# 7_09_6.net
KiCad netlist of a schematic drawn in Altium Designer
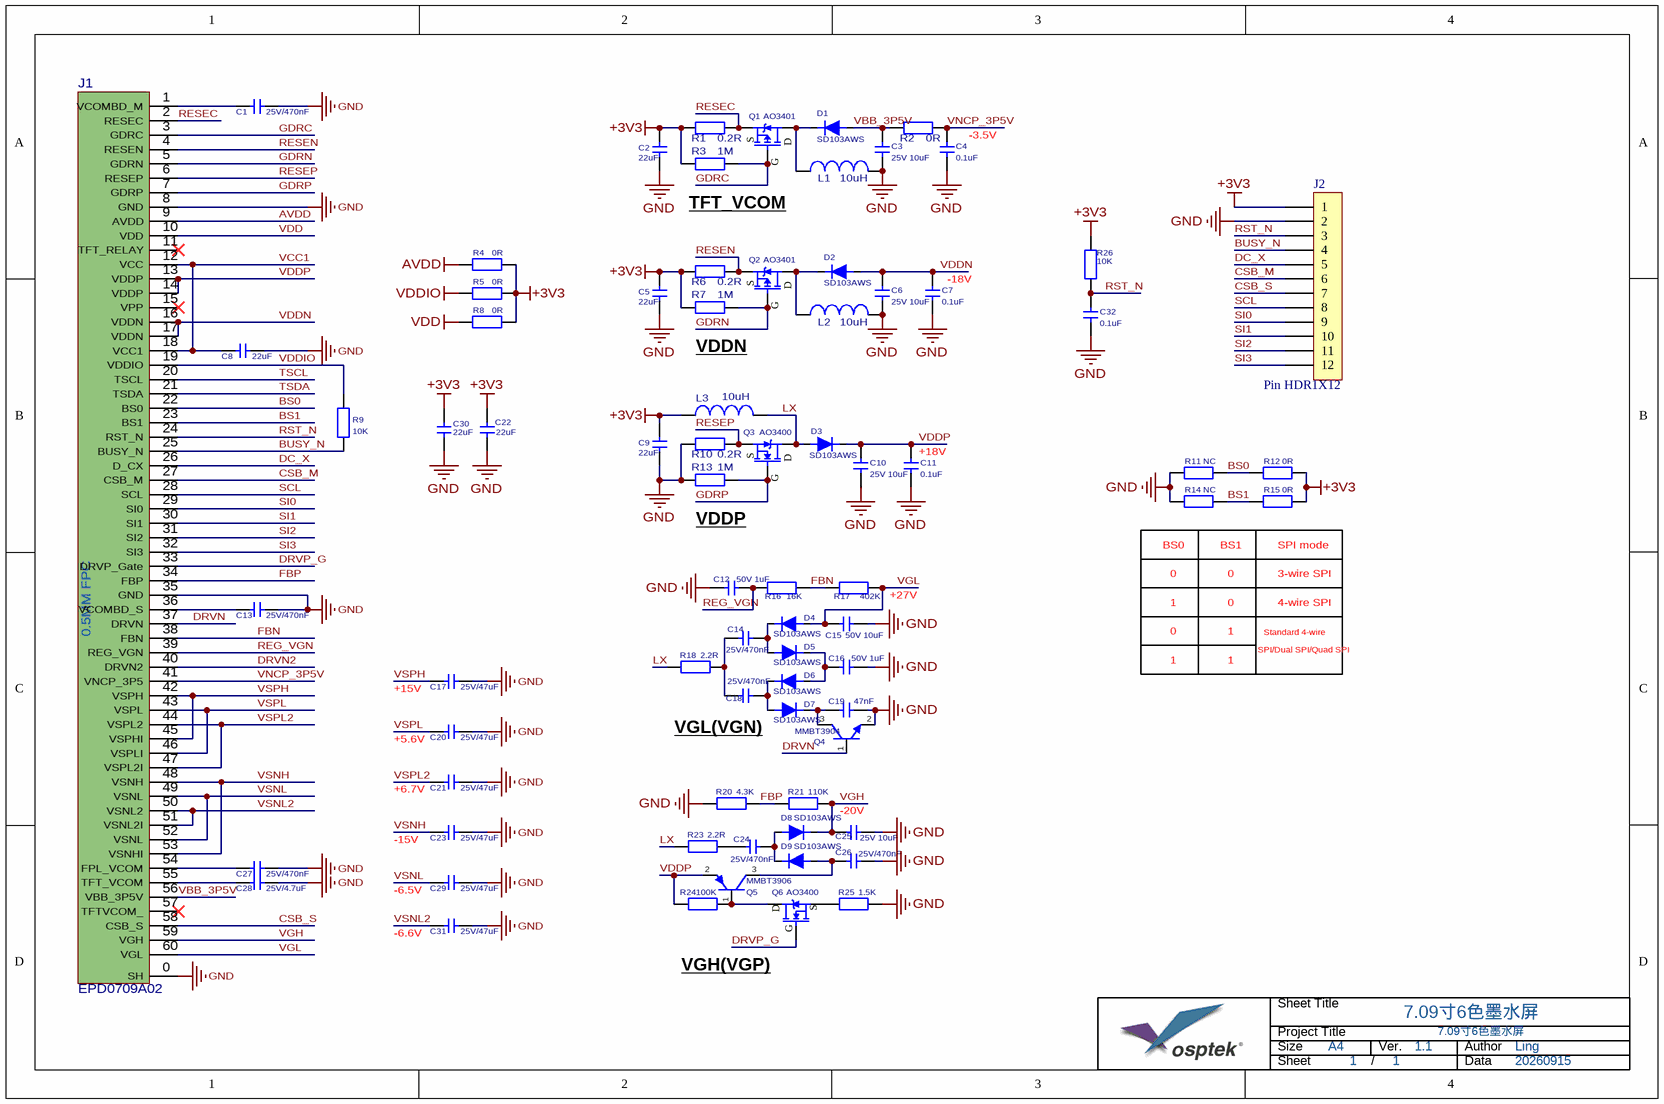
[diagram p0: 7.09寸6色墨水屏.SchDoc]

(export (version "E")
  (design (tool "Eeschema 10.0.6"))
  (components
    (comp (ref "C1")
      (value "25V/470nF")
      (footprint "0603-C")
      (description "Capacitor")
      (libsource (lib "ODG_AD_Lib") (part "CAP"))
    )
    (comp (ref "C2")
      (value "22uF")
      (footprint "0603-C")
      (description "Capacitor")
      (libsource (lib "ODG_AD_Lib") (part "CAP"))
    )
    (comp (ref "C3")
      (value "25V 10uF")
      (footprint "0805-C")
      (description "Capacitor")
      (libsource (lib "ODG_AD_Lib") (part "CAP"))
    )
    (comp (ref "C4")
      (value "0.1uF")
      (footprint "0603-C")
      (description "Capacitor")
      (libsource (lib "ODG_AD_Lib") (part "CAP"))
    )
    (comp (ref "C5")
      (value "22uF")
      (footprint "0603-C")
      (description "Capacitor")
      (libsource (lib "ODG_AD_Lib") (part "CAP"))
    )
    (comp (ref "C6")
      (value "25V 10uF")
      (footprint "0805-C")
      (description "Capacitor")
      (libsource (lib "ODG_AD_Lib") (part "CAP"))
    )
    (comp (ref "C7")
      (value "0.1uF")
      (footprint "0603-C")
      (description "Capacitor")
      (libsource (lib "ODG_AD_Lib") (part "CAP"))
    )
    (comp (ref "C8")
      (value "22uF")
      (footprint "0603-C")
      (description "Capacitor")
      (libsource (lib "ODG_AD_Lib") (part "CAP"))
    )
    (comp (ref "C9")
      (value "22uF")
      (footprint "0603-C")
      (description "Capacitor")
      (libsource (lib "ODG_AD_Lib") (part "CAP"))
    )
    (comp (ref "C10")
      (value "25V 10uF")
      (footprint "0805-C")
      (description "Capacitor")
      (libsource (lib "ODG_AD_Lib") (part "CAP"))
    )
    (comp (ref "C11")
      (value "0.1uF")
      (footprint "0603-C")
      (description "Capacitor")
      (libsource (lib "ODG_AD_Lib") (part "CAP"))
    )
    (comp (ref "C12")
      (value "50V 1uF")
      (footprint "0603-C")
      (description "Capacitor")
      (libsource (lib "ODG_AD_Lib") (part "CAP"))
    )
    (comp (ref "C13")
      (value "25V/470nF")
      (footprint "0603-C")
      (description "Capacitor")
      (libsource (lib "ODG_AD_Lib") (part "CAP"))
    )
    (comp (ref "C14")
      (value "25V/470nF")
      (footprint "0603-C")
      (description "Capacitor")
      (libsource (lib "ODG_AD_Lib") (part "CAP"))
    )
    (comp (ref "C15")
      (value "50V 10uF")
      (footprint "0805-C")
      (description "Capacitor")
      (libsource (lib "ODG_AD_Lib") (part "CAP"))
    )
    (comp (ref "C16")
      (value "50V 1uF")
      (footprint "0603-C")
      (description "Capacitor")
      (libsource (lib "ODG_AD_Lib") (part "CAP"))
    )
    (comp (ref "C17")
      (value "25V/47uF")
      (footprint "1206/3216 C3")
      (description "Capacitor")
      (libsource (lib "ODG_AD_Lib") (part "CAP"))
    )
    (comp (ref "C18")
      (value "25V/470nF")
      (footprint "0603-C")
      (description "Capacitor")
      (libsource (lib "ODG_AD_Lib") (part "CAP"))
    )
    (comp (ref "C19")
      (value "47nF")
      (footprint "0603-C")
      (description "Capacitor")
      (libsource (lib "ODG_AD_Lib") (part "CAP"))
    )
    (comp (ref "C20")
      (value "25V/47uF")
      (footprint "1206/3216 C3")
      (description "Capacitor")
      (libsource (lib "ODG_AD_Lib") (part "CAP"))
    )
    (comp (ref "C21")
      (value "25V/47uF")
      (footprint "1206/3216 C3")
      (description "Capacitor")
      (libsource (lib "ODG_AD_Lib") (part "CAP"))
    )
    (comp (ref "C22")
      (value "22uF")
      (footprint "0603-C")
      (description "Capacitor")
      (libsource (lib "ODG_AD_Lib") (part "CAP"))
    )
    (comp (ref "C23")
      (value "25V/47uF")
      (footprint "1206/3216 C3")
      (description "Capacitor")
      (libsource (lib "ODG_AD_Lib") (part "CAP"))
    )
    (comp (ref "C24")
      (value "25V/470nF")
      (footprint "0603-C")
      (description "Capacitor")
      (libsource (lib "ODG_AD_Lib") (part "CAP"))
    )
    (comp (ref "C25")
      (value "25V 10uF")
      (footprint "0805-C")
      (description "Capacitor")
      (libsource (lib "ODG_AD_Lib") (part "CAP"))
    )
    (comp (ref "C26")
      (value "25V/470nF")
      (footprint "0603-C")
      (description "Capacitor")
      (libsource (lib "ODG_AD_Lib") (part "CAP"))
    )
    (comp (ref "C27")
      (value "25V/470nF")
      (footprint "0603-C")
      (description "Capacitor")
      (libsource (lib "ODG_AD_Lib") (part "CAP"))
    )
    (comp (ref "C28")
      (value "25V/4.7uF")
      (footprint "0603-C")
      (description "Capacitor")
      (libsource (lib "ODG_AD_Lib") (part "CAP"))
    )
    (comp (ref "C29")
      (value "25V/47uF")
      (footprint "1206/3216 C3")
      (description "Capacitor")
      (libsource (lib "ODG_AD_Lib") (part "CAP"))
    )
    (comp (ref "C30")
      (value "22uF")
      (footprint "0603-C")
      (description "Capacitor")
      (libsource (lib "ODG_AD_Lib") (part "CAP"))
    )
    (comp (ref "C31")
      (value "25V/47uF")
      (footprint "1206/3216 C3")
      (description "Capacitor")
      (libsource (lib "ODG_AD_Lib") (part "CAP"))
    )
    (comp (ref "C32")
      (value "0.1uF")
      (footprint "0603-C")
      (description "Capacitor")
      (libsource (lib "ODG_AD_Lib") (part "CAP"))
    )
    (comp (ref "D1") (value "SD103AWS") (footprint "SOD-323") (libsource (lib "CZ-NB部分") (part "DSK110")))
    (comp (ref "D2") (value "SD103AWS") (footprint "SOD-323") (libsource (lib "CZ-NB部分") (part "DSK110")))
    (comp (ref "D3") (value "SD103AWS") (footprint "SOD-323") (libsource (lib "CZ-NB部分") (part "DSK110")))
    (comp (ref "D4") (value "SD103AWS") (footprint "SOD-323") (libsource (lib "CZ-NB部分") (part "DSK110")))
    (comp (ref "D5") (value "SD103AWS") (footprint "SOD-323") (libsource (lib "CZ-NB部分") (part "DSK110")))
    (comp (ref "D6") (value "SD103AWS") (footprint "SOD-323") (libsource (lib "CZ-NB部分") (part "DSK110")))
    (comp (ref "D7") (value "SD103AWS") (footprint "SOD-323") (libsource (lib "CZ-NB部分") (part "DSK110")))
    (comp (ref "D8") (value "SD103AWS") (footprint "SOD-323") (libsource (lib "CZ-NB部分") (part "DSK110")))
    (comp (ref "D9") (value "SD103AWS") (footprint "SOD-323") (libsource (lib "CZ-NB部分") (part "DSK110")))
    (comp (ref "J1")
      (value "EPD0709A02")
      (footprint "FPC0.5-60P")
      (libsource (lib "ESP32P4C5模组") (part "EPD0709A02"))
    )
    (comp (ref "J2")
      (value "Pin HDR1X12")
      (footprint "Pin HDR1X12/2.54mm-S")
      (libsource (lib "排针") (part "Pin HDR1X12"))
    )
    (comp (ref "L1")
      (value "10uH")
      (footprint "IND_CB2518_MM")
      (description "INDUCTOR")
      (libsource (lib "电感") (part "INDUCTOR"))
    )
    (comp (ref "L2")
      (value "10uH")
      (footprint "IND_CB2518_MM")
      (description "INDUCTOR")
      (libsource (lib "电感") (part "INDUCTOR"))
    )
    (comp (ref "L3")
      (value "10uH")
      (footprint "IND_CB2518_MM")
      (description "INDUCTOR")
      (libsource (lib "电感") (part "INDUCTOR"))
    )
    (comp (ref "Q1")
      (value "AO3401")
      (footprint "SOT-23-3")
      (description "P沟道 30V/4.2A")
      (libsource (lib "6.1   - 场效应管-可控硅") (part "AO3401"))
    )
    (comp (ref "Q2")
      (value "AO3401")
      (footprint "SOT-23-3")
      (description "P沟道 30V/4.2A")
      (libsource (lib "6.1   - 场效应管-可控硅") (part "AO3401"))
    )
    (comp (ref "Q3")
      (value "AO3400")
      (footprint "SOT-23-3")
      (description "N沟道 30V/4.2A")
      (libsource (lib "6.1   - 场效应管-可控硅") (part "AO3400"))
    )
    (comp (ref "Q4")
      (value "MMBT3904")
      (footprint "SOT-23-3")
      (description "NPN Bipolar Transistor")
      (fields (field (name "PUBLISHER") "Altium Limited"))
      (libsource (lib "Miscellaneous Devices") (part "NPN"))
    )
    (comp (ref "Q5")
      (value "MMBT3906")
      (footprint "SOT-23-3")
      (description "NPN Bipolar Transistor")
      (fields (field (name "PUBLISHER") "Altium Limited"))
      (libsource (lib "ESP32P4C5模组") (part "PNP"))
    )
    (comp (ref "Q6")
      (value "AO3400")
      (footprint "SOT-23-3")
      (description "N沟道 30V/4.2A")
      (libsource (lib "6.1   - 场效应管-可控硅") (part "AO3400"))
    )
    (comp (ref "R1")
      (value "0.2R")
      (footprint "0603-R")
      (description "Resistor")
      (fields (field (name "PUBLISHER") "*"))
      (libsource (lib "*") (part "Res2"))
    )
    (comp (ref "R2")
      (value "0R")
      (footprint "0603-R")
      (description "Resistor")
      (fields (field (name "PUBLISHER") "*"))
      (libsource (lib "*") (part "Res2"))
    )
    (comp (ref "R3")
      (value "1M")
      (footprint "0603-R")
      (description "Resistor")
      (fields (field (name "PUBLISHER") "*"))
      (libsource (lib "*") (part "Res2"))
    )
    (comp (ref "R4")
      (value "0R")
      (footprint "0603-R")
      (description "Resistor")
      (fields (field (name "PUBLISHER") "*"))
      (libsource (lib "") (part "Res2_1"))
    )
    (comp (ref "R5")
      (value "0R")
      (footprint "0603-R")
      (description "Resistor")
      (fields (field (name "PUBLISHER") "*"))
      (libsource (lib "") (part "Res2_1"))
    )
    (comp (ref "R6")
      (value "0.2R")
      (footprint "0603-R")
      (description "Resistor")
      (fields (field (name "PUBLISHER") "*"))
      (libsource (lib "*") (part "Res2"))
    )
    (comp (ref "R7")
      (value "1M")
      (footprint "0603-R")
      (description "Resistor")
      (fields (field (name "PUBLISHER") "*"))
      (libsource (lib "*") (part "Res2"))
    )
    (comp (ref "R8")
      (value "0R")
      (footprint "0603-R")
      (description "Resistor")
      (fields (field (name "PUBLISHER") "*"))
      (libsource (lib "") (part "Res2_1"))
    )
    (comp (ref "R9")
      (value "10K")
      (footprint "0603-R")
      (description "Resistor")
      (fields (field (name "PUBLISHER") "*"))
      (libsource (lib "") (part "Res2_2"))
    )
    (comp (ref "R10")
      (value "0.2R")
      (footprint "0603-R")
      (description "Resistor")
      (fields (field (name "PUBLISHER") "*"))
      (libsource (lib "*") (part "Res2"))
    )
    (comp (ref "R11")
      (value "NC")
      (footprint "0603-R")
      (description "Resistor")
      (fields (field (name "PUBLISHER") "*"))
      (libsource (lib "") (part "Res2_1"))
    )
    (comp (ref "R12")
      (value "0R")
      (footprint "0603-R")
      (description "Resistor")
      (fields (field (name "PUBLISHER") "*"))
      (libsource (lib "") (part "Res2_1"))
    )
    (comp (ref "R13")
      (value "1M")
      (footprint "0603-R")
      (description "Resistor")
      (fields (field (name "PUBLISHER") "*"))
      (libsource (lib "*") (part "Res2"))
    )
    (comp (ref "R14")
      (value "NC")
      (footprint "0603-R")
      (description "Resistor")
      (fields (field (name "PUBLISHER") "*"))
      (libsource (lib "") (part "Res2_1"))
    )
    (comp (ref "R15")
      (value "0R")
      (footprint "0603-R")
      (description "Resistor")
      (fields (field (name "PUBLISHER") "*"))
      (libsource (lib "") (part "Res2_1"))
    )
    (comp (ref "R16")
      (value "16K")
      (footprint "0603-R")
      (description "Resistor")
      (fields (field (name "PUBLISHER") "*"))
      (libsource (lib "*") (part "Res2"))
    )
    (comp (ref "R17")
      (value "402K")
      (footprint "0603-R")
      (description "Resistor")
      (fields (field (name "PUBLISHER") "*"))
      (libsource (lib "*") (part "Res2"))
    )
    (comp (ref "R18")
      (value "2.2R")
      (footprint "0603-R")
      (description "Resistor")
      (fields (field (name "PUBLISHER") "*"))
      (libsource (lib "*") (part "Res2"))
    )
    (comp (ref "R20")
      (value "4.3K")
      (footprint "0603-R")
      (description "Resistor")
      (fields (field (name "PUBLISHER") "*"))
      (libsource (lib "*") (part "Res2"))
    )
    (comp (ref "R21")
      (value "110K")
      (footprint "0603-R")
      (description "Resistor")
      (fields (field (name "PUBLISHER") "*"))
      (libsource (lib "*") (part "Res2"))
    )
    (comp (ref "R23")
      (value "2.2R")
      (footprint "0603-R")
      (description "Resistor")
      (fields (field (name "PUBLISHER") "*"))
      (libsource (lib "*") (part "Res2"))
    )
    (comp (ref "R24")
      (value "100K")
      (footprint "0603-R")
      (description "Resistor")
      (fields (field (name "PUBLISHER") "*"))
      (libsource (lib "*") (part "Res2"))
    )
    (comp (ref "R25")
      (value "1.5K")
      (footprint "0603-R")
      (description "Resistor")
      (fields (field (name "PUBLISHER") "*"))
      (libsource (lib "*") (part "Res2"))
    )
    (comp (ref "R26")
      (value "10K")
      (footprint "0603-R")
      (description "Resistor")
      (fields (field (name "PUBLISHER") "*"))
      (libsource (lib "") (part "Res2_3"))
    )
  )
  (nets
    (net (code "1") (name "+3V3") (class "Default")
      (node (ref "C2") (pin "2") (pinfunction "2_2") (pintype "passive"))
      (node (ref "C22") (pin "2") (pinfunction "2_2") (pintype "passive"))
      (node (ref "C30") (pin "1") (pinfunction "1_1") (pintype "passive"))
      (node (ref "C5") (pin "2") (pinfunction "2_2") (pintype "passive"))
      (node (ref "C9") (pin "2") (pinfunction "2_2") (pintype "passive"))
      (node (ref "J2") (pin "1") (pinfunction "1_1") (pintype "passive"))
      (node (ref "L3") (pin "2") (pinfunction "2_2") (pintype "passive"))
      (node (ref "R1") (pin "2") (pinfunction "2_2") (pintype "passive"))
      (node (ref "R12") (pin "2") (pinfunction "2_2") (pintype "passive"))
      (node (ref "R15") (pin "2") (pinfunction "2_2") (pintype "passive"))
      (node (ref "R26") (pin "2") (pinfunction "2_2") (pintype "passive"))
      (node (ref "R3") (pin "2") (pinfunction "2_2") (pintype "passive"))
      (node (ref "R4") (pin "2") (pinfunction "2_2") (pintype "passive"))
      (node (ref "R5") (pin "2") (pinfunction "2_2") (pintype "passive"))
      (node (ref "R6") (pin "2") (pinfunction "2_2") (pintype "passive"))
      (node (ref "R7") (pin "2") (pinfunction "2_2") (pintype "passive"))
      (node (ref "R8") (pin "2") (pinfunction "2_2") (pintype "passive"))
    )
    (net (code "2") (name "/BS0") (class "Default")
      (node (ref "J1") (pin "22") (pinfunction "BS0_22") (pintype "passive"))
      (node (ref "R11") (pin "2") (pinfunction "2_2") (pintype "passive"))
      (node (ref "R12") (pin "1") (pinfunction "1_1") (pintype "passive"))
    )
    (net (code "3") (name "/BS1") (class "Default")
      (node (ref "J1") (pin "23") (pinfunction "BS1_23") (pintype "passive"))
      (node (ref "R14") (pin "2") (pinfunction "2_2") (pintype "passive"))
      (node (ref "R15") (pin "1") (pinfunction "1_1") (pintype "passive"))
    )
    (net (code "4") (name "/BUSY_N") (class "Default")
      (node (ref "J1") (pin "25") (pinfunction "BUSY_N_25") (pintype "passive"))
      (node (ref "J2") (pin "4") (pinfunction "4_4") (pintype "passive"))
      (node (ref "R9") (pin "2") (pinfunction "2_2") (pintype "passive"))
    )
    (net (code "5") (name "/CSB_M") (class "Default")
      (node (ref "J1") (pin "27") (pinfunction "CSB_M_27") (pintype "passive"))
      (node (ref "J2") (pin "6") (pinfunction "6_6") (pintype "passive"))
    )
    (net (code "6") (name "/CSB_S") (class "Default")
      (node (ref "J1") (pin "58") (pinfunction "CSB_S_58") (pintype "passive"))
      (node (ref "J2") (pin "7") (pinfunction "7_7") (pintype "passive"))
    )
    (net (code "7") (name "/DC_X") (class "Default")
      (node (ref "J1") (pin "26") (pinfunction "D_CX_26") (pintype "passive"))
      (node (ref "J2") (pin "5") (pinfunction "5_5") (pintype "passive"))
    )
    (net (code "8") (name "/DRVN") (class "Default")
      (node (ref "J1") (pin "37") (pinfunction "DRVN_37") (pintype "passive"))
      (node (ref "Q4") (pin "1") (pinfunction "B_1") (pintype "passive"))
    )
    (net (code "9") (name "/DRVN2") (class "Default")
      (node (ref "J1") (pin "40") (pinfunction "DRVN2_40") (pintype "passive"))
    )
    (net (code "10") (name "/DRVP_G") (class "Default")
      (node (ref "J1") (pin "33") (pinfunction "DRVP_Gate_33") (pintype "passive"))
      (node (ref "Q6") (pin "1") (pinfunction "G_1") (pintype "passive"))
    )
    (net (code "11") (name "/FBN") (class "Default")
      (node (ref "J1") (pin "38") (pinfunction "FBN_38") (pintype "passive"))
      (node (ref "R16") (pin "1") (pinfunction "1_1") (pintype "passive"))
      (node (ref "R17") (pin "2") (pinfunction "2_2") (pintype "passive"))
    )
    (net (code "12") (name "/FBP") (class "Default")
      (node (ref "J1") (pin "34") (pinfunction "FBP_34") (pintype "passive"))
      (node (ref "R20") (pin "1") (pinfunction "1_1") (pintype "passive"))
      (node (ref "R21") (pin "2") (pinfunction "2_2") (pintype "passive"))
    )
    (net (code "13") (name "/GDRC") (class "Default")
      (node (ref "J1") (pin "3") (pinfunction "GDRC_3") (pintype "passive"))
      (node (ref "Q1") (pin "1") (pinfunction "G_1") (pintype "passive"))
      (node (ref "R3") (pin "1") (pinfunction "1_1") (pintype "passive"))
    )
    (net (code "14") (name "/GDRN") (class "Default")
      (node (ref "J1") (pin "5") (pinfunction "GDRN_5") (pintype "passive"))
      (node (ref "Q2") (pin "1") (pinfunction "G_1") (pintype "passive"))
      (node (ref "R7") (pin "1") (pinfunction "1_1") (pintype "passive"))
    )
    (net (code "15") (name "/GDRP") (class "Default")
      (node (ref "J1") (pin "7") (pinfunction "GDRP_7") (pintype "passive"))
      (node (ref "Q3") (pin "1") (pinfunction "G_1") (pintype "passive"))
      (node (ref "R13") (pin "1") (pinfunction "1_1") (pintype "passive"))
    )
    (net (code "16") (name "/LX") (class "Default")
      (node (ref "D3") (pin "A") (pinfunction "A_A") (pintype "passive"))
      (node (ref "L3") (pin "1") (pinfunction "1_1") (pintype "passive"))
      (node (ref "Q3") (pin "3") (pinfunction "D_3") (pintype "passive"))
      (node (ref "R18") (pin "2") (pinfunction "2_2") (pintype "passive"))
      (node (ref "R23") (pin "2") (pinfunction "2_2") (pintype "passive"))
    )
    (net (code "17") (name "/REG_VGN") (class "Default")
      (node (ref "C12") (pin "1") (pinfunction "1_1") (pintype "passive"))
      (node (ref "J1") (pin "39") (pinfunction "REG_VGN_39") (pintype "passive"))
      (node (ref "R16") (pin "2") (pinfunction "2_2") (pintype "passive"))
    )
    (net (code "18") (name "/RESEC") (class "Default")
      (node (ref "J1") (pin "2") (pinfunction "RESEC_2") (pintype "passive"))
      (node (ref "Q1") (pin "2") (pinfunction "S_2") (pintype "passive"))
      (node (ref "R1") (pin "1") (pinfunction "1_1") (pintype "passive"))
    )
    (net (code "19") (name "/RESEN") (class "Default")
      (node (ref "J1") (pin "4") (pinfunction "RESEN_4") (pintype "passive"))
      (node (ref "Q2") (pin "2") (pinfunction "S_2") (pintype "passive"))
      (node (ref "R6") (pin "1") (pinfunction "1_1") (pintype "passive"))
    )
    (net (code "20") (name "/RESEP") (class "Default")
      (node (ref "J1") (pin "6") (pinfunction "RESEP_6") (pintype "passive"))
      (node (ref "Q3") (pin "2") (pinfunction "S_2") (pintype "passive"))
      (node (ref "R10") (pin "1") (pinfunction "1_1") (pintype "passive"))
    )
    (net (code "21") (name "/RST_N") (class "Default")
      (node (ref "C32") (pin "2") (pinfunction "2_2") (pintype "passive"))
      (node (ref "J1") (pin "24") (pinfunction "RST_N_24") (pintype "passive"))
      (node (ref "J2") (pin "3") (pinfunction "3_3") (pintype "passive"))
      (node (ref "R26") (pin "1") (pinfunction "1_1") (pintype "passive"))
    )
    (net (code "22") (name "/SCL") (class "Default")
      (node (ref "J1") (pin "28") (pinfunction "SCL_28") (pintype "passive"))
      (node (ref "J2") (pin "8") (pinfunction "8_8") (pintype "passive"))
    )
    (net (code "23") (name "/SI0") (class "Default")
      (node (ref "J1") (pin "29") (pinfunction "SI0_29") (pintype "passive"))
      (node (ref "J2") (pin "9") (pinfunction "9_9") (pintype "passive"))
    )
    (net (code "24") (name "/SI1") (class "Default")
      (node (ref "J1") (pin "30") (pinfunction "SI1_30") (pintype "passive"))
      (node (ref "J2") (pin "10") (pinfunction "10_10") (pintype "passive"))
    )
    (net (code "25") (name "/SI2") (class "Default")
      (node (ref "J1") (pin "31") (pinfunction "SI2_31") (pintype "passive"))
      (node (ref "J2") (pin "11") (pinfunction "11_11") (pintype "passive"))
    )
    (net (code "26") (name "/SI3") (class "Default")
      (node (ref "J1") (pin "32") (pinfunction "SI3_32") (pintype "passive"))
      (node (ref "J2") (pin "12") (pinfunction "12_12") (pintype "passive"))
    )
    (net (code "27") (name "/TSCL") (class "Default")
      (node (ref "J1") (pin "20") (pinfunction "TSCL_20") (pintype "passive"))
    )
    (net (code "28") (name "/TSDA") (class "Default")
      (node (ref "J1") (pin "21") (pinfunction "TSDA_21") (pintype "passive"))
    )
    (net (code "29") (name "/VBB_3P5V") (class "Default")
      (node (ref "C3") (pin "2") (pinfunction "2_2") (pintype "passive"))
      (node (ref "D1") (pin "A") (pinfunction "A_A") (pintype "passive"))
      (node (ref "J1") (pin "56") (pinfunction "VBB_3P5V_56") (pintype "passive"))
      (node (ref "R2") (pin "2") (pinfunction "2_2") (pintype "passive"))
    )
    (net (code "30") (name "/VCC1") (class "Default")
      (node (ref "C8") (pin "1") (pinfunction "1_1") (pintype "passive"))
      (node (ref "J1") (pin "12") (pinfunction "VCC_12") (pintype "passive"))
      (node (ref "J1") (pin "18") (pinfunction "VCC1_18") (pintype "passive"))
    )
    (net (code "31") (name "/VDDN") (class "Default")
      (node (ref "C6") (pin "2") (pinfunction "2_2") (pintype "passive"))
      (node (ref "C7") (pin "2") (pinfunction "2_2") (pintype "passive"))
      (node (ref "D2") (pin "A") (pinfunction "A_A") (pintype "passive"))
      (node (ref "J1") (pin "16") (pinfunction "VDDN_16") (pintype "passive"))
      (node (ref "J1") (pin "17") (pinfunction "VDDN_17") (pintype "passive"))
    )
    (net (code "32") (name "/VDDP") (class "Default")
      (node (ref "C10") (pin "2") (pinfunction "2_2") (pintype "passive"))
      (node (ref "C11") (pin "2") (pinfunction "2_2") (pintype "passive"))
      (node (ref "D3") (pin "K") (pinfunction "K_K") (pintype "passive"))
      (node (ref "J1") (pin "13") (pinfunction "VDDP_13") (pintype "passive"))
      (node (ref "J1") (pin "14") (pinfunction "VDDP_14") (pintype "passive"))
      (node (ref "Q5") (pin "2") (pinfunction "E_2") (pintype "passive"))
      (node (ref "R24") (pin "2") (pinfunction "2_2") (pintype "passive"))
    )
    (net (code "33") (name "/VGH") (class "Default")
      (node (ref "C25") (pin "2") (pinfunction "2_2") (pintype "passive"))
      (node (ref "D8") (pin "K") (pinfunction "K_K") (pintype "passive"))
      (node (ref "J1") (pin "59") (pinfunction "VGH_59") (pintype "passive"))
      (node (ref "R21") (pin "1") (pinfunction "1_1") (pintype "passive"))
    )
    (net (code "34") (name "/VGL") (class "Default")
      (node (ref "C15") (pin "2") (pinfunction "2_2") (pintype "passive"))
      (node (ref "D4") (pin "A") (pinfunction "A_A") (pintype "passive"))
      (node (ref "J1") (pin "60") (pinfunction "VGL_60") (pintype "passive"))
      (node (ref "R17") (pin "1") (pinfunction "1_1") (pintype "passive"))
    )
    (net (code "35") (name "/VNCP_3P5V") (class "Default")
      (node (ref "C4") (pin "2") (pinfunction "2_2") (pintype "passive"))
      (node (ref "J1") (pin "41") (pinfunction "VNCP_3P5_41") (pintype "passive"))
      (node (ref "R2") (pin "1") (pinfunction "1_1") (pintype "passive"))
    )
    (net (code "36") (name "/VSNH") (class "Default")
      (node (ref "C23") (pin "1") (pinfunction "1_1") (pintype "passive"))
      (node (ref "J1") (pin "48") (pinfunction "VSNH_48") (pintype "passive"))
      (node (ref "J1") (pin "53") (pinfunction "VSNHI_53") (pintype "passive"))
    )
    (net (code "37") (name "/VSNL") (class "Default")
      (node (ref "C29") (pin "1") (pinfunction "1_1") (pintype "passive"))
      (node (ref "J1") (pin "49") (pinfunction "VSNL_49") (pintype "passive"))
      (node (ref "J1") (pin "52") (pinfunction "VSNL_52") (pintype "passive"))
    )
    (net (code "38") (name "/VSNL2") (class "Default")
      (node (ref "C31") (pin "1") (pinfunction "1_1") (pintype "passive"))
      (node (ref "J1") (pin "50") (pinfunction "VSNL2_50") (pintype "passive"))
      (node (ref "J1") (pin "51") (pinfunction "VSNL2I_51") (pintype "passive"))
    )
    (net (code "39") (name "/VSPH") (class "Default")
      (node (ref "C17") (pin "1") (pinfunction "1_1") (pintype "passive"))
      (node (ref "J1") (pin "42") (pinfunction "VSPH_42") (pintype "passive"))
      (node (ref "J1") (pin "45") (pinfunction "VSPHI_45") (pintype "passive"))
    )
    (net (code "40") (name "/VSPL") (class "Default")
      (node (ref "C20") (pin "1") (pinfunction "1_1") (pintype "passive"))
      (node (ref "J1") (pin "43") (pinfunction "VSPL_43") (pintype "passive"))
      (node (ref "J1") (pin "46") (pinfunction "VSPLI_46") (pintype "passive"))
    )
    (net (code "41") (name "/VSPL2") (class "Default")
      (node (ref "C21") (pin "1") (pinfunction "1_1") (pintype "passive"))
      (node (ref "J1") (pin "44") (pinfunction "VSPL2_44") (pintype "passive"))
      (node (ref "J1") (pin "47") (pinfunction "VSPL2I_47") (pintype "passive"))
    )
    (net (code "42") (name "AVDD") (class "Default")
      (node (ref "J1") (pin "9") (pinfunction "AVDD_9") (pintype "passive"))
      (node (ref "R4") (pin "1") (pinfunction "1_1") (pintype "passive"))
    )
    (net (code "43") (name "GND") (class "Default")
      (node (ref "C1") (pin "2") (pinfunction "2_2") (pintype "passive"))
      (node (ref "C10") (pin "1") (pinfunction "1_1") (pintype "passive"))
      (node (ref "C11") (pin "1") (pinfunction "1_1") (pintype "passive"))
      (node (ref "C12") (pin "2") (pinfunction "2_2") (pintype "passive"))
      (node (ref "C13") (pin "2") (pinfunction "2_2") (pintype "passive"))
      (node (ref "C15") (pin "1") (pinfunction "1_1") (pintype "passive"))
      (node (ref "C16") (pin "1") (pinfunction "1_1") (pintype "passive"))
      (node (ref "C17") (pin "2") (pinfunction "2_2") (pintype "passive"))
      (node (ref "C19") (pin "1") (pinfunction "1_1") (pintype "passive"))
      (node (ref "C2") (pin "1") (pinfunction "1_1") (pintype "passive"))
      (node (ref "C20") (pin "2") (pinfunction "2_2") (pintype "passive"))
      (node (ref "C21") (pin "2") (pinfunction "2_2") (pintype "passive"))
      (node (ref "C22") (pin "1") (pinfunction "1_1") (pintype "passive"))
      (node (ref "C23") (pin "2") (pinfunction "2_2") (pintype "passive"))
      (node (ref "C25") (pin "1") (pinfunction "1_1") (pintype "passive"))
      (node (ref "C26") (pin "1") (pinfunction "1_1") (pintype "passive"))
      (node (ref "C27") (pin "2") (pinfunction "2_2") (pintype "passive"))
      (node (ref "C28") (pin "2") (pinfunction "2_2") (pintype "passive"))
      (node (ref "C29") (pin "2") (pinfunction "2_2") (pintype "passive"))
      (node (ref "C3") (pin "1") (pinfunction "1_1") (pintype "passive"))
      (node (ref "C30") (pin "2") (pinfunction "2_2") (pintype "passive"))
      (node (ref "C31") (pin "2") (pinfunction "2_2") (pintype "passive"))
      (node (ref "C32") (pin "1") (pinfunction "1_1") (pintype "passive"))
      (node (ref "C4") (pin "1") (pinfunction "1_1") (pintype "passive"))
      (node (ref "C5") (pin "1") (pinfunction "1_1") (pintype "passive"))
      (node (ref "C6") (pin "1") (pinfunction "1_1") (pintype "passive"))
      (node (ref "C7") (pin "1") (pinfunction "1_1") (pintype "passive"))
      (node (ref "C8") (pin "2") (pinfunction "2_2") (pintype "passive"))
      (node (ref "C9") (pin "1") (pinfunction "1_1") (pintype "passive"))
      (node (ref "J1") (pin "0") (pinfunction "SH_0") (pintype "passive"))
      (node (ref "J1") (pin "35") (pinfunction "GND_35") (pintype "passive"))
      (node (ref "J1") (pin "8") (pinfunction "GND_8") (pintype "passive"))
      (node (ref "J2") (pin "2") (pinfunction "2_2") (pintype "passive"))
      (node (ref "L1") (pin "1") (pinfunction "1_1") (pintype "passive"))
      (node (ref "L2") (pin "1") (pinfunction "1_1") (pintype "passive"))
      (node (ref "Q4") (pin "2") (pinfunction "E_2") (pintype "passive"))
      (node (ref "R10") (pin "2") (pinfunction "2_2") (pintype "passive"))
      (node (ref "R11") (pin "1") (pinfunction "1_1") (pintype "passive"))
      (node (ref "R13") (pin "2") (pinfunction "2_2") (pintype "passive"))
      (node (ref "R14") (pin "1") (pinfunction "1_1") (pintype "passive"))
      (node (ref "R20") (pin "2") (pinfunction "2_2") (pintype "passive"))
      (node (ref "R25") (pin "1") (pinfunction "1_1") (pintype "passive"))
    )
    (net (code "44") (name "Net-(C14-Pad1)") (class "Default")
      (node (ref "C14") (pin "1") (pinfunction "1_1") (pintype "passive"))
      (node (ref "D4") (pin "K") (pinfunction "K_K") (pintype "passive"))
      (node (ref "D5") (pin "A") (pinfunction "A_A") (pintype "passive"))
    )
    (net (code "45") (name "Net-(C14-Pad2)") (class "Default")
      (node (ref "C14") (pin "2") (pinfunction "2_2") (pintype "passive"))
      (node (ref "C18") (pin "2") (pinfunction "2_2") (pintype "passive"))
      (node (ref "R18") (pin "1") (pinfunction "1_1") (pintype "passive"))
    )
    (net (code "46") (name "Net-(C16-Pad2)") (class "Default")
      (node (ref "C16") (pin "2") (pinfunction "2_2") (pintype "passive"))
      (node (ref "D5") (pin "K") (pinfunction "K_K") (pintype "passive"))
      (node (ref "D6") (pin "A") (pinfunction "A_A") (pintype "passive"))
    )
    (net (code "47") (name "Net-(C18-Pad1)") (class "Default")
      (node (ref "C18") (pin "1") (pinfunction "1_1") (pintype "passive"))
      (node (ref "D6") (pin "K") (pinfunction "K_K") (pintype "passive"))
      (node (ref "D7") (pin "A") (pinfunction "A_A") (pintype "passive"))
    )
    (net (code "48") (name "Net-(C24-Pad1)") (class "Default")
      (node (ref "C24") (pin "1") (pinfunction "1_1") (pintype "passive"))
      (node (ref "D8") (pin "A") (pinfunction "A_A") (pintype "passive"))
      (node (ref "D9") (pin "K") (pinfunction "K_K") (pintype "passive"))
    )
    (net (code "49") (name "Net-(C24-Pad2)") (class "Default")
      (node (ref "C24") (pin "2") (pinfunction "2_2") (pintype "passive"))
      (node (ref "R23") (pin "1") (pinfunction "1_1") (pintype "passive"))
    )
    (net (code "50") (name "Net-(J1-FPL_VCOM)") (class "Default")
      (node (ref "C27") (pin "1") (pinfunction "1_1") (pintype "passive"))
      (node (ref "J1") (pin "54") (pinfunction "FPL_VCOM_54") (pintype "passive"))
    )
    (net (code "51") (name "Net-(J1-TFT_VCOM)") (class "Default")
      (node (ref "C28") (pin "1") (pinfunction "1_1") (pintype "passive"))
      (node (ref "J1") (pin "55") (pinfunction "TFT_VCOM_55") (pintype "passive"))
    )
    (net (code "52") (name "Net-(J1-VCOMBD_M)") (class "Default")
      (node (ref "C1") (pin "1") (pinfunction "1_1") (pintype "passive"))
      (node (ref "J1") (pin "1") (pinfunction "VCOMBD_M_1") (pintype "passive"))
    )
    (net (code "53") (name "Net-(J1-VCOMBD_S)") (class "Default")
      (node (ref "C13") (pin "1") (pinfunction "1_1") (pintype "passive"))
      (node (ref "J1") (pin "36") (pinfunction "VCOMBD_S_36") (pintype "passive"))
    )
    (net (code "54") (name "Net-(Q1-D)") (class "Default")
      (node (ref "D1") (pin "K") (pinfunction "K_K") (pintype "passive"))
      (node (ref "L1") (pin "2") (pinfunction "2_2") (pintype "passive"))
      (node (ref "Q1") (pin "3") (pinfunction "D_3") (pintype "passive"))
    )
    (net (code "55") (name "Net-(Q2-D)") (class "Default")
      (node (ref "D2") (pin "K") (pinfunction "K_K") (pintype "passive"))
      (node (ref "L2") (pin "2") (pinfunction "2_2") (pintype "passive"))
      (node (ref "Q2") (pin "3") (pinfunction "D_3") (pintype "passive"))
    )
    (net (code "56") (name "Net-(Q4-C)") (class "Default")
      (node (ref "C19") (pin "2") (pinfunction "2_2") (pintype "passive"))
      (node (ref "D7") (pin "K") (pinfunction "K_K") (pintype "passive"))
      (node (ref "Q4") (pin "3") (pinfunction "C_3") (pintype "passive"))
    )
    (net (code "57") (name "Net-(Q5-B)") (class "Default")
      (node (ref "Q5") (pin "1") (pinfunction "B_1") (pintype "passive"))
      (node (ref "Q6") (pin "3") (pinfunction "D_3") (pintype "passive"))
      (node (ref "R24") (pin "1") (pinfunction "1_1") (pintype "passive"))
    )
    (net (code "58") (name "Net-(Q5-C)") (class "Default")
      (node (ref "C26") (pin "2") (pinfunction "2_2") (pintype "passive"))
      (node (ref "D9") (pin "A") (pinfunction "A_A") (pintype "passive"))
      (node (ref "Q5") (pin "3") (pinfunction "C_3") (pintype "passive"))
    )
    (net (code "59") (name "Net-(Q6-S)") (class "Default")
      (node (ref "Q6") (pin "2") (pinfunction "S_2") (pintype "passive"))
      (node (ref "R25") (pin "2") (pinfunction "2_2") (pintype "passive"))
    )
    (net (code "60") (name "VDD") (class "Default")
      (node (ref "J1") (pin "10") (pinfunction "VDD_10") (pintype "passive"))
      (node (ref "R8") (pin "1") (pinfunction "1_1") (pintype "passive"))
    )
    (net (code "61") (name "VDDIO") (class "Default")
      (node (ref "J1") (pin "19") (pinfunction "VDDIO_19") (pintype "passive"))
      (node (ref "R5") (pin "1") (pinfunction "1_1") (pintype "passive"))
      (node (ref "R9") (pin "1") (pinfunction "1_1") (pintype "passive"))
    )
    (net (code "62") (name "unconnected-(J1-TFTVCOM_-Pad57)") (class "Default")
      (node (ref "J1") (pin "57") (pinfunction "TFTVCOM__57") (pintype "passive+no_connect"))
    )
    (net (code "63") (name "unconnected-(J1-TFT_RELAY-Pad11)") (class "Default")
      (node (ref "J1") (pin "11") (pinfunction "TFT_RELAY_11") (pintype "passive+no_connect"))
    )
    (net (code "64") (name "unconnected-(J1-VPP-Pad15)") (class "Default")
      (node (ref "J1") (pin "15") (pinfunction "VPP_15") (pintype "passive+no_connect"))
    )
  )
)
